# X-DO10_V1_0.net
KiCad netlist of a schematic drawn in Altium Designer
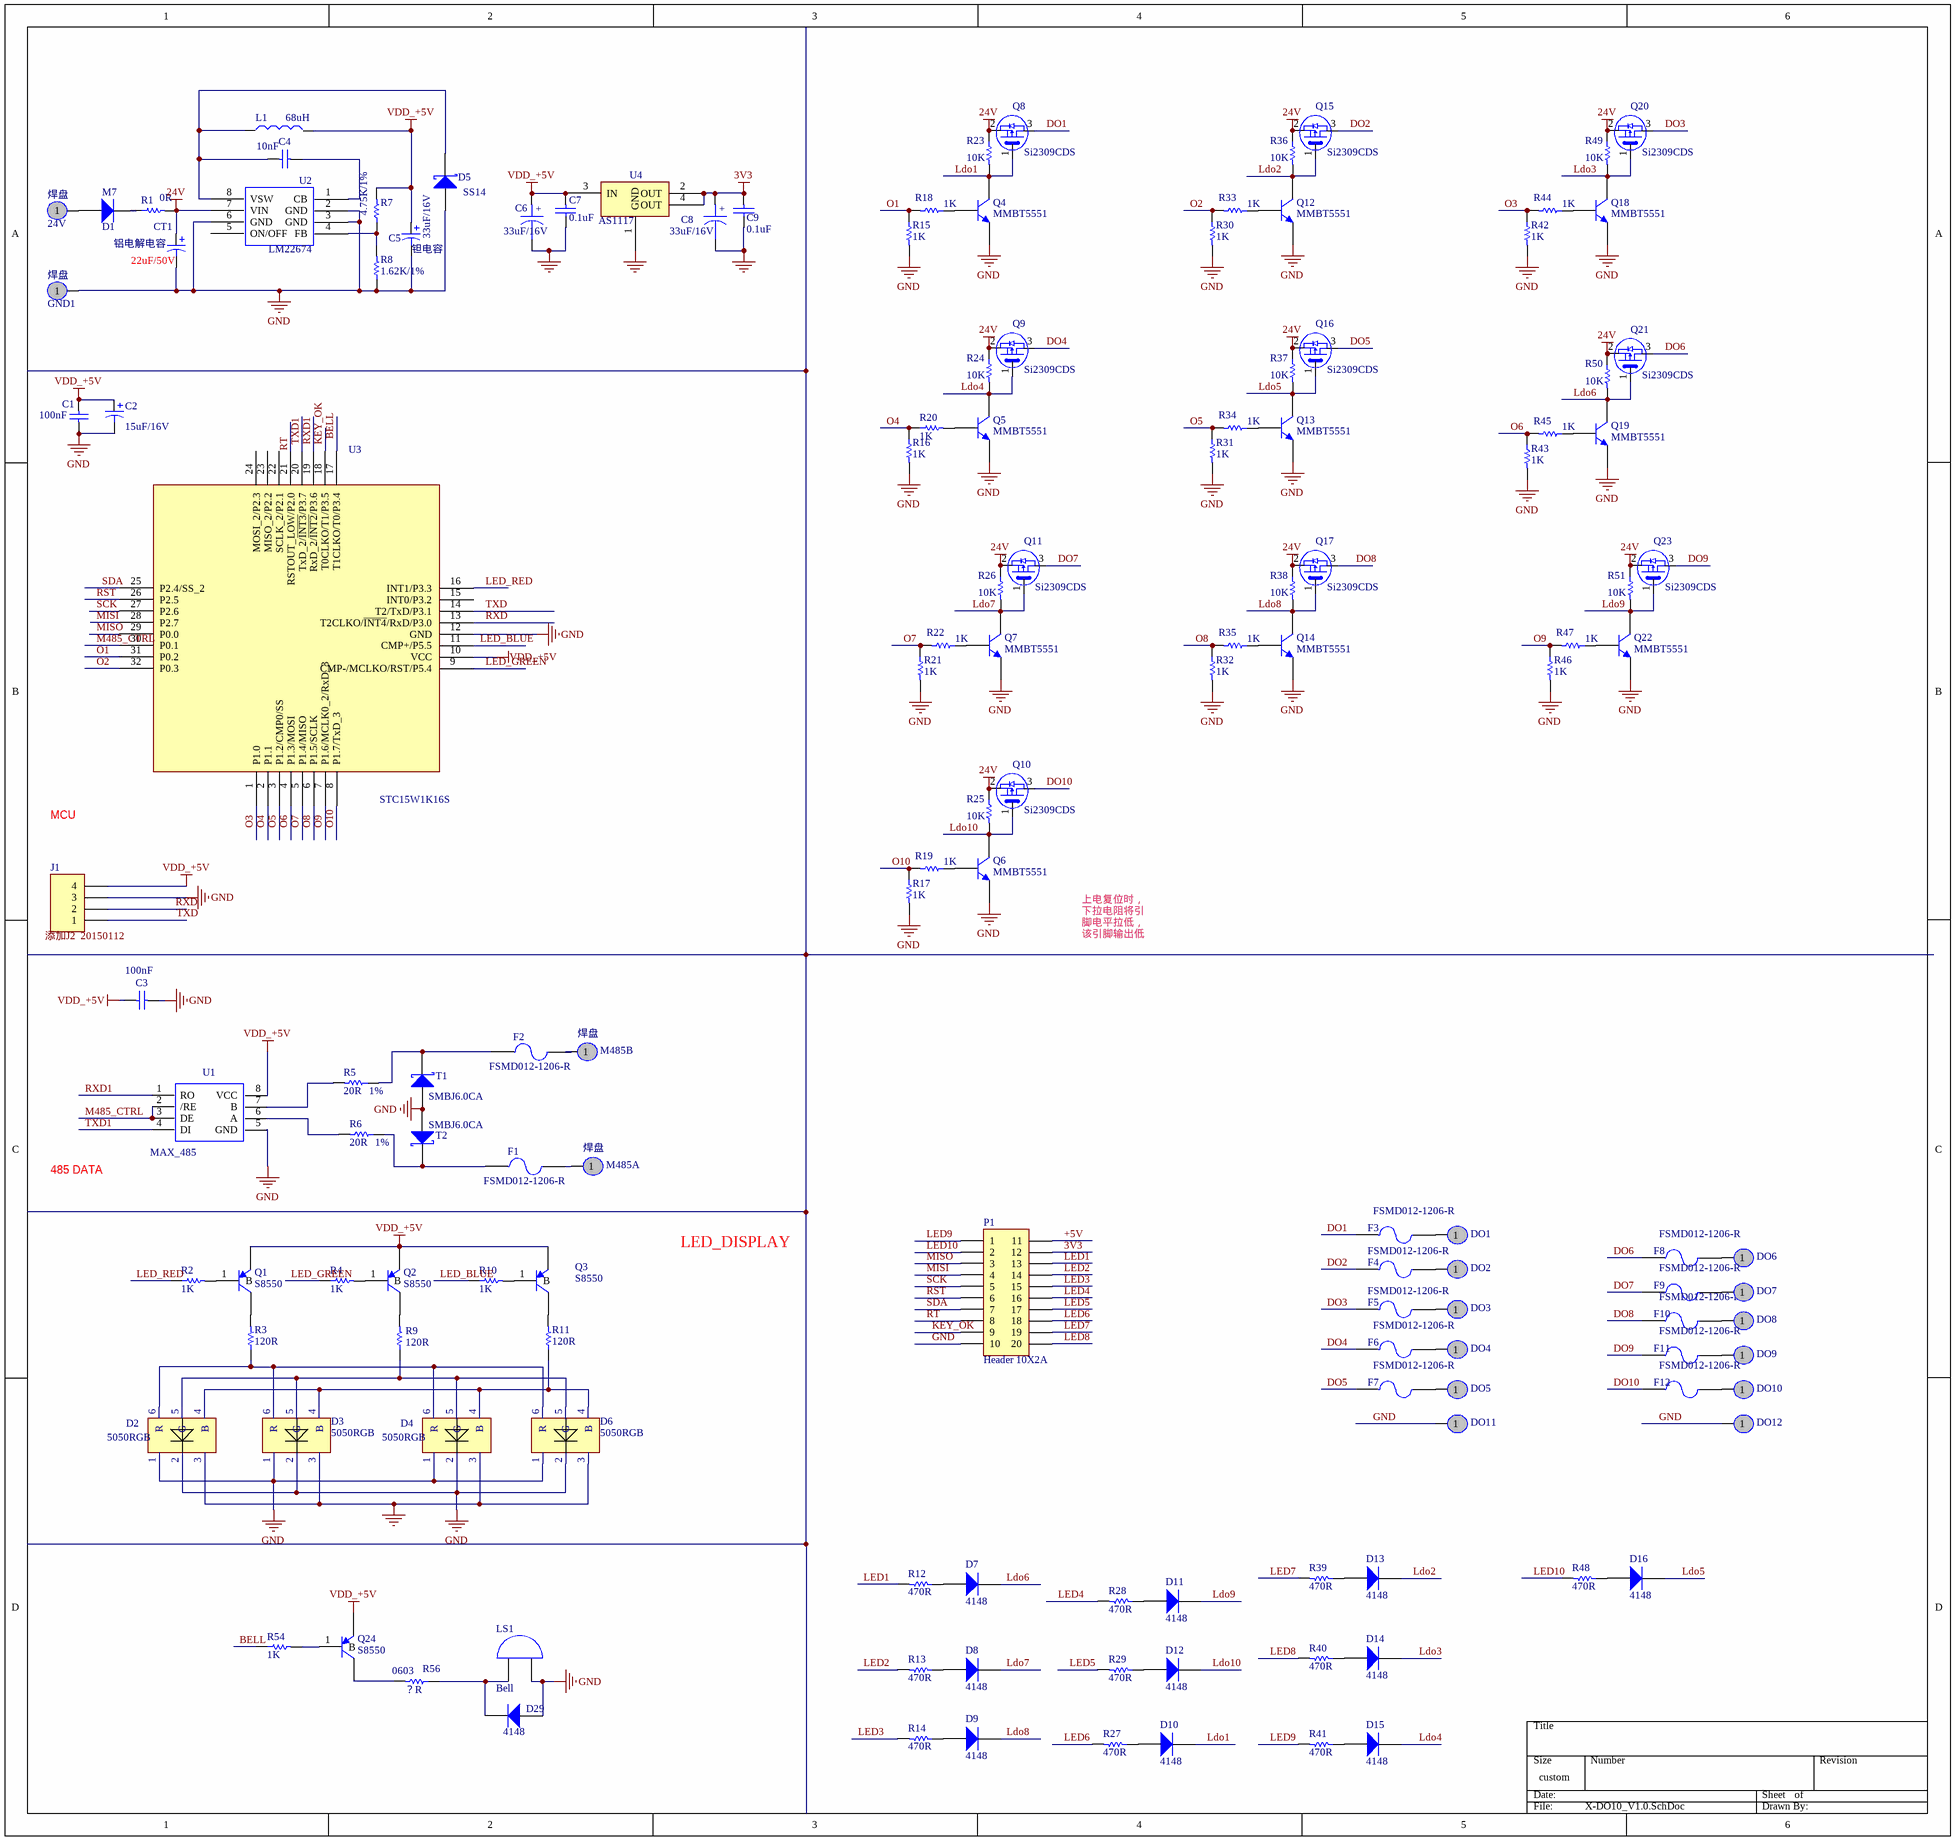
[diagram p0: X-DO10_V1.0.SchDoc]

(export (version "E")
  (design (tool "Eeschema 10.0.6"))
  (components
    (comp (ref "24V") (value "焊盘") (footprint "HOLE_SMD") (libsource (lib "MODBUS_V1.0") (part "焊盘")))
    (comp (ref "C1")
      (value "100nF")
      (footprint "C0603")
      (description "Capacitor")
      (libsource (lib "Miscellaneous Devices") (part "Cap"))
    )
    (comp (ref "C2")
      (value "15uF/16V")
      (footprint "1206C")
      (description "Polarized Capacitor (Radial)")
      (libsource (lib "Miscellaneous Devices") (part "Cap Pol1"))
    )
    (comp (ref "C3")
      (value "~")
      (footprint "C0603")
      (description "Capacitor")
      (fields (field (name "ALTIUM_UNNAMED_1") "100nF"))
      (libsource (lib "Miscellaneous Devices") (part "Cap"))
    )
    (comp (ref "C4")
      (value "~")
      (footprint "C0603")
      (description "Capacitor")
      (fields (field (name "ALTIUM_UNNAMED_1") "10nF"))
      (libsource (lib "Miscellaneous Devices") (part "Cap"))
    )
    (comp (ref "C5")
      (value "钽电容")
      (footprint "CT3528")
      (description "Polarized Capacitor (Radial)")
      (fields (field (name "ALTIUM_VALUE") "33uF/16V"))
      (libsource (lib "Miscellaneous Devices") (part "Cap Pol1"))
    )
    (comp (ref "C6")
      (value "33uF/16V")
      (footprint "CT3528")
      (description "Capacitor")
      (libsource (lib "*") (part "CAPACITOR POL"))
    )
    (comp (ref "C7")
      (value "0.1uF")
      (footprint "C0603")
      (description "Capacitor")
      (libsource (lib "*") (part "CAP"))
    )
    (comp (ref "C8")
      (value "33uF/16V")
      (footprint "CT3528")
      (description "Capacitor")
      (libsource (lib "*") (part "CAPACITOR POL"))
    )
    (comp (ref "C9")
      (value "0.1uF")
      (footprint "C0603")
      (description "Capacitor")
      (libsource (lib "*") (part "CAP"))
    )
    (comp (ref "CT1")
      (value "铝电解电容")
      (footprint "RB0.1")
      (description "Polarized Capacitor (Radial)")
      (fields (field (name "ALTIUM_UNNAMED_1") "22uF/50V"))
      (libsource (lib "Miscellaneous Devices") (part "Cap Pol1"))
    )
    (comp (ref "D1")
      (value "~")
      (footprint "SMB")
      (description "Default Diode")
      (fields (field (name "ALTIUM_UNNAMED_1") "M7"))
      (libsource (lib "Miscellaneous Devices") (part "Diode"))
    )
    (comp (ref "D2") (value "5050RGB") (footprint "5050RGB") (libsource (lib "*") (part "5050RGB")))
    (comp (ref "D3") (value "5050RGB") (footprint "5050RGB") (libsource (lib "*") (part "5050RGB")))
    (comp (ref "D4") (value "5050RGB") (footprint "5050RGB") (libsource (lib "*") (part "5050RGB")))
    (comp (ref "D5")
      (value "~")
      (footprint "SMB")
      (fields (field (name "ALTIUM_UNNAMED_1") "SS14"))
      (libsource (lib "MODBUS_V1.0") (part "SMBJ6.0CA"))
    )
    (comp (ref "D6") (value "5050RGB") (footprint "5050RGB") (libsource (lib "*") (part "5050RGB")))
    (comp (ref "D7")
      (value "~")
      (footprint "1206d")
      (description "Default Diode")
      (fields (field (name "ALTIUM_UNNAMED_1") "4148"))
      (libsource (lib "Miscellaneous Devices") (part "Diode"))
    )
    (comp (ref "D8")
      (value "~")
      (footprint "1206d")
      (description "Default Diode")
      (fields (field (name "ALTIUM_UNNAMED_1") "4148"))
      (libsource (lib "Miscellaneous Devices") (part "Diode"))
    )
    (comp (ref "D9")
      (value "~")
      (footprint "1206d")
      (description "Default Diode")
      (fields (field (name "ALTIUM_UNNAMED_1") "4148"))
      (libsource (lib "Miscellaneous Devices") (part "Diode"))
    )
    (comp (ref "D10")
      (value "~")
      (footprint "1206d")
      (description "Default Diode")
      (fields (field (name "ALTIUM_UNNAMED_1") "4148"))
      (libsource (lib "Miscellaneous Devices") (part "Diode"))
    )
    (comp (ref "D11")
      (value "~")
      (footprint "1206d")
      (description "Default Diode")
      (fields (field (name "ALTIUM_UNNAMED_1") "4148"))
      (libsource (lib "Miscellaneous Devices") (part "Diode"))
    )
    (comp (ref "D12")
      (value "~")
      (footprint "1206d")
      (description "Default Diode")
      (fields (field (name "ALTIUM_UNNAMED_1") "4148"))
      (libsource (lib "Miscellaneous Devices") (part "Diode"))
    )
    (comp (ref "D13")
      (value "~")
      (footprint "1206d")
      (description "Default Diode")
      (fields (field (name "ALTIUM_UNNAMED_1") "4148"))
      (libsource (lib "Miscellaneous Devices") (part "Diode"))
    )
    (comp (ref "D14")
      (value "~")
      (footprint "1206d")
      (description "Default Diode")
      (fields (field (name "ALTIUM_UNNAMED_1") "4148"))
      (libsource (lib "Miscellaneous Devices") (part "Diode"))
    )
    (comp (ref "D15")
      (value "~")
      (footprint "1206d")
      (description "Default Diode")
      (fields (field (name "ALTIUM_UNNAMED_1") "4148"))
      (libsource (lib "Miscellaneous Devices") (part "Diode"))
    )
    (comp (ref "D16")
      (value "~")
      (footprint "1206D")
      (description "Default Diode")
      (fields (field (name "ALTIUM_UNNAMED_1") "4148"))
      (libsource (lib "Miscellaneous Devices") (part "Diode"))
    )
    (comp (ref "D29")
      (value "4148")
      (footprint "MODBUS_V2.0:1206D")
      (description "Default Diode")
      (fields (field (name "PUBLISHER") "Altium Limited"))
      (libsource (lib "Miscellaneous Devices") (part "Diode"))
    )
    (comp (ref "DO1")
      (value "焊盘")
      (footprint "MODBUS_V1.0:HOLE_SMD")
      (libsource (lib "MODBUS_V1.0") (part "焊盘"))
    )
    (comp (ref "DO2")
      (value "焊盘")
      (footprint "MODBUS_V1.0:HOLE_SMD")
      (libsource (lib "MODBUS_V1.0") (part "焊盘"))
    )
    (comp (ref "DO3") (value "焊盘") (footprint "HOLE_SMD") (libsource (lib "MODBUS_V1.0") (part "焊盘")))
    (comp (ref "DO4") (value "焊盘") (footprint "HOLE_SMD") (libsource (lib "MODBUS_V1.0") (part "焊盘")))
    (comp (ref "DO5") (value "焊盘") (footprint "HOLE_SMD") (libsource (lib "MODBUS_V1.0") (part "焊盘")))
    (comp (ref "DO6") (value "焊盘") (footprint "HOLE_SMD") (libsource (lib "MODBUS_V1.0") (part "焊盘")))
    (comp (ref "DO7")
      (value "焊盘")
      (footprint "MODBUS_V1.0:HOLE_SMD")
      (libsource (lib "MODBUS_V1.0") (part "焊盘"))
    )
    (comp (ref "DO8") (value "焊盘") (footprint "HOLE_SMD") (libsource (lib "MODBUS_V1.0") (part "焊盘")))
    (comp (ref "DO9") (value "焊盘") (footprint "HOLE_SMD") (libsource (lib "MODBUS_V1.0") (part "焊盘")))
    (comp (ref "DO10") (value "焊盘") (footprint "HOLE_SMD") (libsource (lib "MODBUS_V1.0") (part "焊盘")))
    (comp (ref "DO11") (value "焊盘") (footprint "HOLE_SMD") (libsource (lib "MODBUS_V1.0") (part "焊盘")))
    (comp (ref "DO12") (value "焊盘") (footprint "HOLE_SMD") (libsource (lib "MODBUS_V1.0") (part "焊盘")))
    (comp (ref "F1")
      (value "FSMD012-1206-R")
      (footprint "1206")
      (description "Fuse")
      (fields (field (name "ALTIUM_UNNAMED_1") "FSMD012-1206-R"))
      (libsource (lib "Miscellaneous Devices") (part "Fuse 2"))
    )
    (comp (ref "F2")
      (value "FSMD012-1206-R")
      (footprint "1206")
      (description "Fuse")
      (fields (field (name "ALTIUM_UNNAMED_1") "FSMD012-1206-R"))
      (libsource (lib "Miscellaneous Devices") (part "Fuse 2"))
    )
    (comp (ref "F3")
      (value "FSMD012-1206-R")
      (footprint "1206")
      (description "Fuse")
      (libsource (lib "Miscellaneous Devices") (part "Fuse 2"))
    )
    (comp (ref "F4")
      (value "FSMD012-1206-R")
      (footprint "1206")
      (description "Fuse")
      (libsource (lib "Miscellaneous Devices") (part "Fuse 2"))
    )
    (comp (ref "F5")
      (value "FSMD012-1206-R")
      (footprint "1206")
      (description "Fuse")
      (libsource (lib "Miscellaneous Devices") (part "Fuse 2"))
    )
    (comp (ref "F6")
      (value "FSMD012-1206-R")
      (footprint "1206")
      (description "Fuse")
      (libsource (lib "Miscellaneous Devices") (part "Fuse 2"))
    )
    (comp (ref "F7")
      (value "FSMD012-1206-R")
      (footprint "1206")
      (description "Fuse")
      (libsource (lib "Miscellaneous Devices") (part "Fuse 2"))
    )
    (comp (ref "F8")
      (value "FSMD012-1206-R")
      (footprint "1206")
      (description "Fuse")
      (libsource (lib "Miscellaneous Devices") (part "Fuse 2"))
    )
    (comp (ref "F9")
      (value "FSMD012-1206-R")
      (footprint "1206")
      (description "Fuse")
      (libsource (lib "Miscellaneous Devices") (part "Fuse 2"))
    )
    (comp (ref "F10")
      (value "FSMD012-1206-R")
      (footprint "1206")
      (description "Fuse")
      (libsource (lib "Miscellaneous Devices") (part "Fuse 2"))
    )
    (comp (ref "F11")
      (value "FSMD012-1206-R")
      (footprint "1206")
      (description "Fuse")
      (libsource (lib "Miscellaneous Devices") (part "Fuse 2"))
    )
    (comp (ref "F12")
      (value "FSMD012-1206-R")
      (footprint "1206")
      (description "Fuse")
      (libsource (lib "Miscellaneous Devices") (part "Fuse 2"))
    )
    (comp (ref "GND1") (value "焊盘") (footprint "HOLE_SMD") (libsource (lib "MODBUS_V1.0") (part "焊盘")))
    (comp (ref "J1")
      (value "~")
      (footprint "SIP4-2.0")
      (libsource (lib "Miscellaneous Connectors") (part "Header 4"))
    )
    (comp (ref "L1")
      (value "~")
      (footprint "L-6X6")
      (fields (field (name "ALTIUM_UNNAMED_1") "68uH"))
      (libsource (lib "MODBUS_V1.0") (part "电感"))
    )
    (comp (ref "LS1")
      (value "Bell")
      (footprint "Bell_DIP_9mm")
      (description "Electrical Bell")
      (fields (field (name "PUBLISHER") "Altium Limited"))
      (libsource (lib "Miscellaneous Devices") (part "Bell"))
    )
    (comp (ref "M485A") (value "焊盘") (footprint "HOLE_SMD") (libsource (lib "MODBUS_V1.0") (part "焊盘")))
    (comp (ref "M485B") (value "焊盘") (footprint "HOLE_SMD") (libsource (lib "MODBUS_V1.0") (part "焊盘")))
    (comp (ref "P1")
      (value "Header 10X2A")
      (footprint "DIP2.0 2*10")
      (description "Header, 10-Pin, Dual row")
      (fields (field (name "PUBLISHER") "Altium Limited"))
      (libsource (lib "Miscellaneous Connectors") (part "Header 10X2A"))
    )
    (comp (ref "Q1") (value "S8550") (footprint "SOT-23") (libsource (lib "*") (part "S8550")))
    (comp (ref "Q2") (value "S8550") (footprint "SOT-23") (libsource (lib "*") (part "S8550")))
    (comp (ref "Q3") (value "S8550") (footprint "SOT-23") (libsource (lib "*") (part "S8550")))
    (comp (ref "Q4")
      (value "MMBT5551")
      (footprint "SOT-23")
      (description "NPN Bipolar Transistor")
      (fields (field (name "PUBLISHER") "Altium Limited"))
      (libsource (lib "Miscellaneous Devices") (part "NPN"))
    )
    (comp (ref "Q5")
      (value "MMBT5551")
      (footprint "SOT-23")
      (description "NPN Bipolar Transistor")
      (fields (field (name "PUBLISHER") "Altium Limited"))
      (libsource (lib "Miscellaneous Devices") (part "NPN"))
    )
    (comp (ref "Q6")
      (value "MMBT5551")
      (footprint "SOT-23")
      (description "NPN Bipolar Transistor")
      (fields (field (name "PUBLISHER") "Altium Limited"))
      (libsource (lib "Miscellaneous Devices") (part "NPN"))
    )
    (comp (ref "Q7")
      (value "MMBT5551")
      (footprint "SOT-23")
      (description "NPN Bipolar Transistor")
      (fields (field (name "PUBLISHER") "Altium Limited"))
      (libsource (lib "Miscellaneous Devices") (part "NPN"))
    )
    (comp (ref "Q8") (value "Si2309CDS") (footprint "SOT-23") (libsource (lib "BATTERY") (part "P-MOSFET")))
    (comp (ref "Q9") (value "Si2309CDS") (footprint "SOT-23") (libsource (lib "BATTERY") (part "P-MOSFET")))
    (comp (ref "Q10") (value "Si2309CDS") (footprint "SOT-23") (libsource (lib "BATTERY") (part "P-MOSFET")))
    (comp (ref "Q11") (value "Si2309CDS") (footprint "SOT-23") (libsource (lib "BATTERY") (part "P-MOSFET")))
    (comp (ref "Q12")
      (value "MMBT5551")
      (footprint "SOT-23")
      (description "NPN Bipolar Transistor")
      (fields (field (name "PUBLISHER") "Altium Limited"))
      (libsource (lib "Miscellaneous Devices") (part "NPN"))
    )
    (comp (ref "Q13")
      (value "MMBT5551")
      (footprint "SOT-23")
      (description "NPN Bipolar Transistor")
      (fields (field (name "PUBLISHER") "Altium Limited"))
      (libsource (lib "Miscellaneous Devices") (part "NPN"))
    )
    (comp (ref "Q14")
      (value "MMBT5551")
      (footprint "SOT-23")
      (description "NPN Bipolar Transistor")
      (fields (field (name "PUBLISHER") "Altium Limited"))
      (libsource (lib "Miscellaneous Devices") (part "NPN"))
    )
    (comp (ref "Q15") (value "Si2309CDS") (footprint "SOT-23") (libsource (lib "BATTERY") (part "P-MOSFET")))
    (comp (ref "Q16") (value "Si2309CDS") (footprint "SOT-23") (libsource (lib "BATTERY") (part "P-MOSFET")))
    (comp (ref "Q17") (value "Si2309CDS") (footprint "SOT-23") (libsource (lib "BATTERY") (part "P-MOSFET")))
    (comp (ref "Q18")
      (value "MMBT5551")
      (footprint "SOT-23")
      (description "NPN Bipolar Transistor")
      (fields (field (name "PUBLISHER") "Altium Limited"))
      (libsource (lib "Miscellaneous Devices") (part "NPN"))
    )
    (comp (ref "Q19")
      (value "MMBT5551")
      (footprint "SOT-23")
      (description "NPN Bipolar Transistor")
      (fields (field (name "PUBLISHER") "Altium Limited"))
      (libsource (lib "Miscellaneous Devices") (part "NPN"))
    )
    (comp (ref "Q20") (value "Si2309CDS") (footprint "SOT-23") (libsource (lib "BATTERY") (part "P-MOSFET")))
    (comp (ref "Q21") (value "Si2309CDS") (footprint "SOT-23") (libsource (lib "BATTERY") (part "P-MOSFET")))
    (comp (ref "Q22")
      (value "MMBT5551")
      (footprint "SOT-23")
      (description "NPN Bipolar Transistor")
      (fields (field (name "PUBLISHER") "Altium Limited"))
      (libsource (lib "Miscellaneous Devices") (part "NPN"))
    )
    (comp (ref "Q23") (value "Si2309CDS") (footprint "SOT-23") (libsource (lib "BATTERY") (part "P-MOSFET")))
    (comp (ref "Q24") (value "S8550") (footprint "SOT-23") (libsource (lib "MODBUS_V1.0") (part "S8550")))
    (comp (ref "R1")
      (value "贴片电阻")
      (footprint "1206")
      (description "Semiconductor Resistor")
      (fields (field (name "ALTIUM_UNNAMED_1") "0R"))
      (libsource (lib "Miscellaneous Devices") (part "Res Semi"))
    )
    (comp (ref "R2")
      (value "1K")
      (footprint "R0603")
      (description "Semiconductor Resistor")
      (libsource (lib "*") (part "Res Semi"))
    )
    (comp (ref "R3")
      (value "120R")
      (footprint "2010")
      (description "Semiconductor Resistor")
      (libsource (lib "*") (part "Res Semi"))
    )
    (comp (ref "R4")
      (value "1K")
      (footprint "R0603")
      (description "Semiconductor Resistor")
      (libsource (lib "*") (part "Res Semi"))
    )
    (comp (ref "R5")
      (value "~")
      (footprint "2010")
      (description "Semiconductor Resistor")
      (fields (field (name "ALTIUM_UNNAMED_1") "20R   1%"))
      (libsource (lib "Miscellaneous Devices") (part "Res Semi"))
    )
    (comp (ref "R6")
      (value "~")
      (footprint "2010")
      (description "Semiconductor Resistor")
      (fields (field (name "ALTIUM_UNNAMED_1") "20R   1%"))
      (libsource (lib "Miscellaneous Devices") (part "Res Semi"))
    )
    (comp (ref "R7")
      (value "~")
      (footprint "R0603")
      (description "Semiconductor Resistor")
      (fields (field (name "ALTIUM_UNNAMED_1") "4.75K/1%"))
      (libsource (lib "Miscellaneous Devices") (part "Res Semi"))
    )
    (comp (ref "R8")
      (value "~")
      (footprint "R0603")
      (description "Semiconductor Resistor")
      (fields (field (name "V") "1.62K/1%"))
      (libsource (lib "Miscellaneous Devices") (part "Res Semi"))
    )
    (comp (ref "R9")
      (value "120R")
      (footprint "2010")
      (description "Semiconductor Resistor")
      (libsource (lib "*") (part "Res Semi"))
    )
    (comp (ref "R10")
      (value "1K")
      (footprint "R0603")
      (description "Semiconductor Resistor")
      (libsource (lib "*") (part "Res Semi"))
    )
    (comp (ref "R11")
      (value "120R")
      (footprint "2010")
      (description "Semiconductor Resistor")
      (libsource (lib "*") (part "Res Semi"))
    )
    (comp (ref "R12")
      (value "~")
      (footprint "r0603")
      (description "贴片电阻")
      (fields (field (name "型号") "470R"))
      (libsource (lib "Miscellaneous Devices") (part "Res Semi"))
    )
    (comp (ref "R13")
      (value "~")
      (footprint "r0603")
      (description "贴片电阻")
      (fields (field (name "型号") "470R"))
      (libsource (lib "Miscellaneous Devices") (part "Res Semi"))
    )
    (comp (ref "R14")
      (value "~")
      (footprint "r0603")
      (description "贴片电阻")
      (fields (field (name "型号") "470R"))
      (libsource (lib "Miscellaneous Devices") (part "Res Semi"))
    )
    (comp (ref "R15")
      (value "贴片电阻")
      (footprint "R0603")
      (description "Semiconductor Resistor")
      (fields (field (name "ALTIUM_UNNAMED_1") "1K"))
      (libsource (lib "Miscellaneous Devices") (part "Res Semi"))
    )
    (comp (ref "R16")
      (value "贴片电阻")
      (footprint "R0603")
      (description "Semiconductor Resistor")
      (fields (field (name "ALTIUM_UNNAMED_1") "1K"))
      (libsource (lib "Miscellaneous Devices") (part "Res Semi"))
    )
    (comp (ref "R17")
      (value "贴片电阻")
      (footprint "R0603")
      (description "Semiconductor Resistor")
      (fields (field (name "ALTIUM_UNNAMED_1") "1K"))
      (libsource (lib "Miscellaneous Devices") (part "Res Semi"))
    )
    (comp (ref "R18")
      (value "贴片电阻")
      (footprint "R0603")
      (description "Semiconductor Resistor")
      (fields (field (name "ALTIUM_UNNAMED_1") "1K"))
      (libsource (lib "Miscellaneous Devices") (part "Res Semi"))
    )
    (comp (ref "R19")
      (value "贴片电阻")
      (footprint "R0603")
      (description "Semiconductor Resistor")
      (fields (field (name "ALTIUM_UNNAMED_1") "1K"))
      (libsource (lib "Miscellaneous Devices") (part "Res Semi"))
    )
    (comp (ref "R20")
      (value "贴片电阻")
      (footprint "R0603")
      (description "Semiconductor Resistor")
      (fields (field (name "ALTIUM_UNNAMED_1") "1K"))
      (libsource (lib "Miscellaneous Devices") (part "Res Semi"))
    )
    (comp (ref "R21")
      (value "贴片电阻")
      (footprint "R0603")
      (description "Semiconductor Resistor")
      (fields (field (name "ALTIUM_UNNAMED_1") "1K"))
      (libsource (lib "Miscellaneous Devices") (part "Res Semi"))
    )
    (comp (ref "R22")
      (value "贴片电阻")
      (footprint "R0603")
      (description "Semiconductor Resistor")
      (fields (field (name "ALTIUM_UNNAMED_1") "1K"))
      (libsource (lib "Miscellaneous Devices") (part "Res Semi"))
    )
    (comp (ref "R23")
      (value "贴片电阻")
      (footprint "R0603")
      (description "Semiconductor Resistor")
      (fields (field (name "ALTIUM_UNNAMED_1") "10K"))
      (libsource (lib "Miscellaneous Devices") (part "Res Semi"))
    )
    (comp (ref "R24")
      (value "贴片电阻")
      (footprint "R0603")
      (description "Semiconductor Resistor")
      (fields (field (name "ALTIUM_UNNAMED_1") "10K"))
      (libsource (lib "Miscellaneous Devices") (part "Res Semi"))
    )
    (comp (ref "R25")
      (value "贴片电阻")
      (footprint "R0603")
      (description "Semiconductor Resistor")
      (fields (field (name "ALTIUM_UNNAMED_1") "10K"))
      (libsource (lib "Miscellaneous Devices") (part "Res Semi"))
    )
    (comp (ref "R26")
      (value "贴片电阻")
      (footprint "R0603")
      (description "Semiconductor Resistor")
      (fields (field (name "ALTIUM_UNNAMED_1") "10K"))
      (libsource (lib "Miscellaneous Devices") (part "Res Semi"))
    )
    (comp (ref "R27")
      (value "~")
      (footprint "r0603")
      (description "贴片电阻")
      (fields (field (name "型号") "470R"))
      (libsource (lib "Miscellaneous Devices") (part "Res Semi"))
    )
    (comp (ref "R28")
      (value "~")
      (footprint "r0603")
      (description "贴片电阻")
      (fields (field (name "型号") "470R"))
      (libsource (lib "Miscellaneous Devices") (part "Res Semi"))
    )
    (comp (ref "R29")
      (value "~")
      (footprint "r0603")
      (description "贴片电阻")
      (fields (field (name "型号") "470R"))
      (libsource (lib "Miscellaneous Devices") (part "Res Semi"))
    )
    (comp (ref "R30")
      (value "贴片电阻")
      (footprint "R0603")
      (description "Semiconductor Resistor")
      (fields (field (name "ALTIUM_UNNAMED_1") "1K"))
      (libsource (lib "Miscellaneous Devices") (part "Res Semi"))
    )
    (comp (ref "R31")
      (value "贴片电阻")
      (footprint "R0603")
      (description "Semiconductor Resistor")
      (fields (field (name "ALTIUM_UNNAMED_1") "1K"))
      (libsource (lib "Miscellaneous Devices") (part "Res Semi"))
    )
    (comp (ref "R32")
      (value "贴片电阻")
      (footprint "R0603")
      (description "Semiconductor Resistor")
      (fields (field (name "ALTIUM_UNNAMED_1") "1K"))
      (libsource (lib "Miscellaneous Devices") (part "Res Semi"))
    )
    (comp (ref "R33")
      (value "贴片电阻")
      (footprint "R0603")
      (description "Semiconductor Resistor")
      (fields (field (name "ALTIUM_UNNAMED_1") "1K"))
      (libsource (lib "Miscellaneous Devices") (part "Res Semi"))
    )
    (comp (ref "R34")
      (value "贴片电阻")
      (footprint "R0603")
      (description "Semiconductor Resistor")
      (fields (field (name "ALTIUM_UNNAMED_1") "1K"))
      (libsource (lib "Miscellaneous Devices") (part "Res Semi"))
    )
    (comp (ref "R35")
      (value "贴片电阻")
      (footprint "R0603")
      (description "Semiconductor Resistor")
      (fields (field (name "ALTIUM_UNNAMED_1") "1K"))
      (libsource (lib "Miscellaneous Devices") (part "Res Semi"))
    )
    (comp (ref "R36")
      (value "贴片电阻")
      (footprint "R0603")
      (description "Semiconductor Resistor")
      (fields (field (name "ALTIUM_UNNAMED_1") "10K"))
      (libsource (lib "Miscellaneous Devices") (part "Res Semi"))
    )
    (comp (ref "R37")
      (value "贴片电阻")
      (footprint "R0603")
      (description "Semiconductor Resistor")
      (fields (field (name "ALTIUM_UNNAMED_1") "10K"))
      (libsource (lib "Miscellaneous Devices") (part "Res Semi"))
    )
    (comp (ref "R38")
      (value "贴片电阻")
      (footprint "R0603")
      (description "Semiconductor Resistor")
      (fields (field (name "ALTIUM_UNNAMED_1") "10K"))
      (libsource (lib "Miscellaneous Devices") (part "Res Semi"))
    )
    (comp (ref "R39")
      (value "~")
      (footprint "r0603")
      (description "贴片电阻")
      (fields (field (name "型号") "470R"))
      (libsource (lib "Miscellaneous Devices") (part "Res Semi"))
    )
    (comp (ref "R40")
      (value "~")
      (footprint "r0603")
      (description "贴片电阻")
      (fields (field (name "型号") "470R"))
      (libsource (lib "Miscellaneous Devices") (part "Res Semi"))
    )
    (comp (ref "R41")
      (value "~")
      (footprint "r0603")
      (description "贴片电阻")
      (fields (field (name "型号") "470R"))
      (libsource (lib "Miscellaneous Devices") (part "Res Semi"))
    )
    (comp (ref "R42")
      (value "贴片电阻")
      (footprint "R0603")
      (description "Semiconductor Resistor")
      (fields (field (name "ALTIUM_UNNAMED_1") "1K"))
      (libsource (lib "Miscellaneous Devices") (part "Res Semi"))
    )
    (comp (ref "R43")
      (value "贴片电阻")
      (footprint "R0603")
      (description "Semiconductor Resistor")
      (fields (field (name "ALTIUM_UNNAMED_1") "1K"))
      (libsource (lib "Miscellaneous Devices") (part "Res Semi"))
    )
    (comp (ref "R44")
      (value "贴片电阻")
      (footprint "R0603")
      (description "Semiconductor Resistor")
      (fields (field (name "ALTIUM_UNNAMED_1") "1K"))
      (libsource (lib "Miscellaneous Devices") (part "Res Semi"))
    )
    (comp (ref "R45")
      (value "贴片电阻")
      (footprint "R0603")
      (description "Semiconductor Resistor")
      (fields (field (name "ALTIUM_UNNAMED_1") "1K"))
      (libsource (lib "Miscellaneous Devices") (part "Res Semi"))
    )
    (comp (ref "R46")
      (value "贴片电阻")
      (footprint "R0603")
      (description "Semiconductor Resistor")
      (fields (field (name "ALTIUM_UNNAMED_1") "1K"))
      (libsource (lib "Miscellaneous Devices") (part "Res Semi"))
    )
    (comp (ref "R47")
      (value "贴片电阻")
      (footprint "R0603")
      (description "Semiconductor Resistor")
      (fields (field (name "ALTIUM_UNNAMED_1") "1K"))
      (libsource (lib "Miscellaneous Devices") (part "Res Semi"))
    )
    (comp (ref "R48")
      (value "~")
      (footprint "r0603")
      (description "贴片电阻")
      (fields (field (name "型号") "470R"))
      (libsource (lib "Miscellaneous Devices") (part "Res Semi"))
    )
    (comp (ref "R49")
      (value "贴片电阻")
      (footprint "R0603")
      (description "Semiconductor Resistor")
      (fields (field (name "ALTIUM_UNNAMED_1") "10K"))
      (libsource (lib "Miscellaneous Devices") (part "Res Semi"))
    )
    (comp (ref "R50")
      (value "贴片电阻")
      (footprint "R0603")
      (description "Semiconductor Resistor")
      (fields (field (name "ALTIUM_UNNAMED_1") "10K"))
      (libsource (lib "Miscellaneous Devices") (part "Res Semi"))
    )
    (comp (ref "R51")
      (value "贴片电阻")
      (footprint "R0603")
      (description "Semiconductor Resistor")
      (fields (field (name "ALTIUM_UNNAMED_1") "10K"))
      (libsource (lib "Miscellaneous Devices") (part "Res Semi"))
    )
    (comp (ref "R54")
      (value "1K")
      (footprint "R0603")
      (description "Semiconductor Resistor")
      (fields (field (name "PUBLISHER") "Altium Limited"))
      (libsource (lib "Miscellaneous Devices") (part "Res Semi"))
    )
    (comp (ref "R56")
      (value "0603")
      (footprint "R0603")
      (description "Semiconductor Resistor")
      (fields (field (name "ALTIUM_UNNAMED_1") "？R"))
      (libsource (lib "Miscellaneous Devices") (part "Res Semi"))
    )
    (comp (ref "T1")
      (value "SMBJ6.0CA")
      (footprint "HSMA")
      (fields (field (name "ALTIUM_UNNAMED_1") "SMBJ6.0CA"))
      (libsource (lib "MODBUS_V1.0") (part "SMBJ6.0CA"))
    )
    (comp (ref "T2")
      (value "SMBJ6.0CA")
      (footprint "HSMA")
      (fields (field (name "ALTIUM_UNNAMED_1") "SMBJ6.0CA"))
      (libsource (lib "MODBUS_V1.0") (part "SMBJ6.0CA"))
    )
    (comp (ref "U1")
      (value "MAX_485")
      (footprint "SO-1.27-8/4.0")
      (fields (field (name "ALTIUM_UNNAMED_1") "MAX_485"))
      (libsource (lib "*") (part "MAX_485"))
    )
    (comp (ref "U2")
      (value "LM22674")
      (footprint "SO-1.27-9/4.0")
      (fields (field (name "ALTIUM_UNNAMED_1") "LM22674"))
      (libsource (lib "*") (part "2674"))
    )
    (comp (ref "U3")
      (value "STC15W1K16S")
      (footprint "LQFP-0.8-32/9X9")
      (fields (field (name "ALTIUM_UNNAMED_1") "STC15W1K16S"))
      (libsource (lib "MODBUS_V1.0") (part "STC15W1K16S"))
    )
    (comp (ref "U4") (value "AS1117") (footprint "1117") (libsource (lib "*") (part "AS1117")))
  )
  (nets
    (net (code "1") (name "/+5V") (class "Default")
      (node (ref "P1") (pin "11") (pinfunction "11_11") (pintype "passive"))
    )
    (net (code "2") (name "/BELL") (class "Default")
      (node (ref "R54") (pin "1") (pinfunction "1_1") (pintype "passive"))
      (node (ref "U3") (pin "17") (pinfunction "T1CLKO/T0/P3.4_17") (pintype "passive"))
    )
    (net (code "3") (name "/DO1") (class "Default")
      (node (ref "F3") (pin "1") (pinfunction "1_1") (pintype "passive"))
      (node (ref "Q8") (pin "3") (pinfunction "D_3") (pintype "passive"))
    )
    (net (code "4") (name "/DO2") (class "Default")
      (node (ref "F4") (pin "1") (pinfunction "1_1") (pintype "passive"))
      (node (ref "Q15") (pin "3") (pinfunction "D_3") (pintype "passive"))
    )
    (net (code "5") (name "/DO3") (class "Default")
      (node (ref "F5") (pin "1") (pinfunction "1_1") (pintype "passive"))
      (node (ref "Q20") (pin "3") (pinfunction "D_3") (pintype "passive"))
    )
    (net (code "6") (name "/DO4") (class "Default")
      (node (ref "F6") (pin "1") (pinfunction "1_1") (pintype "passive"))
      (node (ref "Q9") (pin "3") (pinfunction "D_3") (pintype "passive"))
    )
    (net (code "7") (name "/DO5") (class "Default")
      (node (ref "F7") (pin "1") (pinfunction "1_1") (pintype "passive"))
      (node (ref "Q16") (pin "3") (pinfunction "D_3") (pintype "passive"))
    )
    (net (code "8") (name "/DO6") (class "Default")
      (node (ref "F8") (pin "1") (pinfunction "1_1") (pintype "passive"))
      (node (ref "Q21") (pin "3") (pinfunction "D_3") (pintype "passive"))
    )
    (net (code "9") (name "/DO7") (class "Default")
      (node (ref "F9") (pin "1") (pinfunction "1_1") (pintype "passive"))
      (node (ref "Q11") (pin "3") (pinfunction "D_3") (pintype "passive"))
    )
    (net (code "10") (name "/DO8") (class "Default")
      (node (ref "F10") (pin "1") (pinfunction "1_1") (pintype "passive"))
      (node (ref "Q17") (pin "3") (pinfunction "D_3") (pintype "passive"))
    )
    (net (code "11") (name "/DO9") (class "Default")
      (node (ref "F11") (pin "1") (pinfunction "1_1") (pintype "passive"))
      (node (ref "Q23") (pin "3") (pinfunction "D_3") (pintype "passive"))
    )
    (net (code "12") (name "/DO10") (class "Default")
      (node (ref "F12") (pin "1") (pinfunction "1_1") (pintype "passive"))
      (node (ref "Q10") (pin "3") (pinfunction "D_3") (pintype "passive"))
    )
    (net (code "13") (name "/KEY_OK") (class "Default")
      (node (ref "P1") (pin "9") (pinfunction "9_9") (pintype "passive"))
      (node (ref "U3") (pin "18") (pinfunction "T0CLKO/T1/P3.5_18") (pintype "passive"))
    )
    (net (code "14") (name "/LED1") (class "Default")
      (node (ref "P1") (pin "13") (pinfunction "13_13") (pintype "passive"))
      (node (ref "R12") (pin "2") (pinfunction "2_2") (pintype "passive"))
    )
    (net (code "15") (name "/LED2") (class "Default")
      (node (ref "P1") (pin "14") (pinfunction "14_14") (pintype "passive"))
      (node (ref "R13") (pin "2") (pinfunction "2_2") (pintype "passive"))
    )
    (net (code "16") (name "/LED3") (class "Default")
      (node (ref "P1") (pin "15") (pinfunction "15_15") (pintype "passive"))
      (node (ref "R14") (pin "2") (pinfunction "2_2") (pintype "passive"))
    )
    (net (code "17") (name "/LED4") (class "Default")
      (node (ref "P1") (pin "16") (pinfunction "16_16") (pintype "passive"))
      (node (ref "R28") (pin "2") (pinfunction "2_2") (pintype "passive"))
    )
    (net (code "18") (name "/LED5") (class "Default")
      (node (ref "P1") (pin "17") (pinfunction "17_17") (pintype "passive"))
      (node (ref "R29") (pin "2") (pinfunction "2_2") (pintype "passive"))
    )
    (net (code "19") (name "/LED6") (class "Default")
      (node (ref "P1") (pin "18") (pinfunction "18_18") (pintype "passive"))
      (node (ref "R27") (pin "2") (pinfunction "2_2") (pintype "passive"))
    )
    (net (code "20") (name "/LED7") (class "Default")
      (node (ref "P1") (pin "19") (pinfunction "19_19") (pintype "passive"))
      (node (ref "R39") (pin "2") (pinfunction "2_2") (pintype "passive"))
    )
    (net (code "21") (name "/LED8") (class "Default")
      (node (ref "P1") (pin "20") (pinfunction "20_20") (pintype "passive"))
      (node (ref "R40") (pin "2") (pinfunction "2_2") (pintype "passive"))
    )
    (net (code "22") (name "/LED9") (class "Default")
      (node (ref "P1") (pin "1") (pinfunction "1_1") (pintype "passive"))
      (node (ref "R41") (pin "2") (pinfunction "2_2") (pintype "passive"))
    )
    (net (code "23") (name "/LED10") (class "Default")
      (node (ref "P1") (pin "2") (pinfunction "2_2") (pintype "passive"))
      (node (ref "R48") (pin "2") (pinfunction "2_2") (pintype "passive"))
    )
    (net (code "24") (name "/LED_BLUE") (class "Default")
      (node (ref "R10") (pin "1") (pinfunction "1_1") (pintype "passive"))
      (node (ref "U3") (pin "11") (pinfunction "CMP+/P5.5_11") (pintype "passive"))
    )
    (net (code "25") (name "/LED_GREEN") (class "Default")
      (node (ref "R4") (pin "1") (pinfunction "1_1") (pintype "passive"))
      (node (ref "U3") (pin "9") (pinfunction "CMP-/MCLKO/RST/P5.4_9") (pintype "passive"))
    )
    (net (code "26") (name "/LED_RED") (class "Default")
      (node (ref "R2") (pin "1") (pinfunction "1_1") (pintype "passive"))
      (node (ref "U3") (pin "16") (pinfunction "INT1/P3.3_16") (pintype "passive"))
    )
    (net (code "27") (name "/Ldo1") (class "Default")
      (node (ref "D10") (pin "2") (pinfunction "K_2") (pintype "passive"))
      (node (ref "Q4") (pin "3") (pinfunction "C_3") (pintype "passive"))
      (node (ref "Q8") (pin "1") (pinfunction "G_1") (pintype "passive"))
      (node (ref "R23") (pin "2") (pinfunction "2_2") (pintype "passive"))
    )
    (net (code "28") (name "/Ldo2") (class "Default")
      (node (ref "D13") (pin "2") (pinfunction "K_2") (pintype "passive"))
      (node (ref "Q12") (pin "3") (pinfunction "C_3") (pintype "passive"))
      (node (ref "Q15") (pin "1") (pinfunction "G_1") (pintype "passive"))
      (node (ref "R36") (pin "2") (pinfunction "2_2") (pintype "passive"))
    )
    (net (code "29") (name "/Ldo3") (class "Default")
      (node (ref "D14") (pin "2") (pinfunction "K_2") (pintype "passive"))
      (node (ref "Q18") (pin "3") (pinfunction "C_3") (pintype "passive"))
      (node (ref "Q20") (pin "1") (pinfunction "G_1") (pintype "passive"))
      (node (ref "R49") (pin "2") (pinfunction "2_2") (pintype "passive"))
    )
    (net (code "30") (name "/Ldo4") (class "Default")
      (node (ref "D15") (pin "2") (pinfunction "K_2") (pintype "passive"))
      (node (ref "Q5") (pin "3") (pinfunction "C_3") (pintype "passive"))
      (node (ref "Q9") (pin "1") (pinfunction "G_1") (pintype "passive"))
      (node (ref "R24") (pin "2") (pinfunction "2_2") (pintype "passive"))
    )
    (net (code "31") (name "/Ldo5") (class "Default")
      (node (ref "D16") (pin "2") (pinfunction "K_2") (pintype "passive"))
      (node (ref "Q13") (pin "3") (pinfunction "C_3") (pintype "passive"))
      (node (ref "Q16") (pin "1") (pinfunction "G_1") (pintype "passive"))
      (node (ref "R37") (pin "2") (pinfunction "2_2") (pintype "passive"))
    )
    (net (code "32") (name "/Ldo6") (class "Default")
      (node (ref "D7") (pin "2") (pinfunction "K_2") (pintype "passive"))
      (node (ref "Q19") (pin "3") (pinfunction "C_3") (pintype "passive"))
      (node (ref "Q21") (pin "1") (pinfunction "G_1") (pintype "passive"))
      (node (ref "R50") (pin "2") (pinfunction "2_2") (pintype "passive"))
    )
    (net (code "33") (name "/Ldo7") (class "Default")
      (node (ref "D8") (pin "2") (pinfunction "K_2") (pintype "passive"))
      (node (ref "Q11") (pin "1") (pinfunction "G_1") (pintype "passive"))
      (node (ref "Q7") (pin "3") (pinfunction "C_3") (pintype "passive"))
      (node (ref "R26") (pin "2") (pinfunction "2_2") (pintype "passive"))
    )
    (net (code "34") (name "/Ldo8") (class "Default")
      (node (ref "D9") (pin "2") (pinfunction "K_2") (pintype "passive"))
      (node (ref "Q14") (pin "3") (pinfunction "C_3") (pintype "passive"))
      (node (ref "Q17") (pin "1") (pinfunction "G_1") (pintype "passive"))
      (node (ref "R38") (pin "2") (pinfunction "2_2") (pintype "passive"))
    )
    (net (code "35") (name "/Ldo9") (class "Default")
      (node (ref "D11") (pin "2") (pinfunction "K_2") (pintype "passive"))
      (node (ref "Q22") (pin "3") (pinfunction "C_3") (pintype "passive"))
      (node (ref "Q23") (pin "1") (pinfunction "G_1") (pintype "passive"))
      (node (ref "R51") (pin "2") (pinfunction "2_2") (pintype "passive"))
    )
    (net (code "36") (name "/Ldo10") (class "Default")
      (node (ref "D12") (pin "2") (pinfunction "K_2") (pintype "passive"))
      (node (ref "Q10") (pin "1") (pinfunction "G_1") (pintype "passive"))
      (node (ref "Q6") (pin "3") (pinfunction "C_3") (pintype "passive"))
      (node (ref "R25") (pin "2") (pinfunction "2_2") (pintype "passive"))
    )
    (net (code "37") (name "/M485_CTRL") (class "Default")
      (node (ref "U1") (pin "2") (pinfunction "/RE_2") (pintype "passive"))
      (node (ref "U1") (pin "3") (pinfunction "DE_3") (pintype "passive"))
      (node (ref "U3") (pin "30") (pinfunction "P0.1_30") (pintype "passive"))
    )
    (net (code "38") (name "/MISI") (class "Default")
      (node (ref "P1") (pin "4") (pinfunction "4_4") (pintype "passive"))
      (node (ref "U3") (pin "28") (pinfunction "P2.7_28") (pintype "passive"))
    )
    (net (code "39") (name "/MISO") (class "Default")
      (node (ref "P1") (pin "3") (pinfunction "3_3") (pintype "passive"))
      (node (ref "U3") (pin "29") (pinfunction "P0.0_29") (pintype "passive"))
    )
    (net (code "40") (name "/O1") (class "Default")
      (node (ref "R15") (pin "1") (pinfunction "1_1") (pintype "passive"))
      (node (ref "R18") (pin "2") (pinfunction "2_2") (pintype "passive"))
      (node (ref "U3") (pin "31") (pinfunction "P0.2_31") (pintype "passive"))
    )
    (net (code "41") (name "/O2") (class "Default")
      (node (ref "R30") (pin "1") (pinfunction "1_1") (pintype "passive"))
      (node (ref "R33") (pin "2") (pinfunction "2_2") (pintype "passive"))
      (node (ref "U3") (pin "32") (pinfunction "P0.3_32") (pintype "passive"))
    )
    (net (code "42") (name "/O3") (class "Default")
      (node (ref "R42") (pin "1") (pinfunction "1_1") (pintype "passive"))
      (node (ref "R44") (pin "2") (pinfunction "2_2") (pintype "passive"))
      (node (ref "U3") (pin "1") (pinfunction "P1.0_1") (pintype "passive"))
    )
    (net (code "43") (name "/O4") (class "Default")
      (node (ref "R16") (pin "1") (pinfunction "1_1") (pintype "passive"))
      (node (ref "R20") (pin "1") (pinfunction "1_1") (pintype "passive"))
      (node (ref "U3") (pin "2") (pinfunction "P1.1_2") (pintype "passive"))
    )
    (net (code "44") (name "/O5") (class "Default")
      (node (ref "R31") (pin "1") (pinfunction "1_1") (pintype "passive"))
      (node (ref "R34") (pin "2") (pinfunction "2_2") (pintype "passive"))
      (node (ref "U3") (pin "3") (pinfunction "P1.2/CMP0/SS_3") (pintype "passive"))
    )
    (net (code "45") (name "/O6") (class "Default")
      (node (ref "R43") (pin "1") (pinfunction "1_1") (pintype "passive"))
      (node (ref "R45") (pin "2") (pinfunction "2_2") (pintype "passive"))
      (node (ref "U3") (pin "4") (pinfunction "P1.3/MOSI_4") (pintype "passive"))
    )
    (net (code "46") (name "/O7") (class "Default")
      (node (ref "R21") (pin "1") (pinfunction "1_1") (pintype "passive"))
      (node (ref "R22") (pin "2") (pinfunction "2_2") (pintype "passive"))
      (node (ref "U3") (pin "5") (pinfunction "P1.4/MISO_5") (pintype "passive"))
    )
    (net (code "47") (name "/O8") (class "Default")
      (node (ref "R32") (pin "1") (pinfunction "1_1") (pintype "passive"))
      (node (ref "R35") (pin "2") (pinfunction "2_2") (pintype "passive"))
      (node (ref "U3") (pin "6") (pinfunction "P1.5/SCLK_6") (pintype "passive"))
    )
    (net (code "48") (name "/O9") (class "Default")
      (node (ref "R46") (pin "1") (pinfunction "1_1") (pintype "passive"))
      (node (ref "R47") (pin "2") (pinfunction "2_2") (pintype "passive"))
      (node (ref "U3") (pin "7") (pinfunction "P1.6/MCLK0_2/RxD_3_7") (pintype "passive"))
    )
    (net (code "49") (name "/O10") (class "Default")
      (node (ref "R17") (pin "1") (pinfunction "1_1") (pintype "passive"))
      (node (ref "R19") (pin "2") (pinfunction "2_2") (pintype "passive"))
      (node (ref "U3") (pin "8") (pinfunction "P1.7/TxD_3_8") (pintype "passive"))
    )
    (net (code "50") (name "/RST") (class "Default")
      (node (ref "P1") (pin "6") (pinfunction "6_6") (pintype "passive"))
      (node (ref "U3") (pin "26") (pinfunction "P2.5_26") (pintype "passive"))
    )
    (net (code "51") (name "/RT") (class "Default")
      (node (ref "P1") (pin "8") (pinfunction "8_8") (pintype "passive"))
      (node (ref "U3") (pin "21") (pinfunction "RSTOUT_LOW/P2.0_21") (pintype "passive"))
    )
    (net (code "52") (name "/RXD") (class "Default")
      (node (ref "J1") (pin "2") (pinfunction "2_2") (pintype "passive"))
      (node (ref "U3") (pin "13") (pinfunction "T2CLKO/~{INT4}/RxD/P3.0_13") (pintype "passive"))
    )
    (net (code "53") (name "/RXD1") (class "Default")
      (node (ref "U1") (pin "1") (pinfunction "RO_1") (pintype "passive"))
      (node (ref "U3") (pin "19") (pinfunction "RxD_2/~{INT2}/P3.6_19") (pintype "passive"))
    )
    (net (code "54") (name "/SCK") (class "Default")
      (node (ref "P1") (pin "5") (pinfunction "5_5") (pintype "passive"))
      (node (ref "U3") (pin "27") (pinfunction "P2.6_27") (pintype "passive"))
    )
    (net (code "55") (name "/SDA") (class "Default")
      (node (ref "P1") (pin "7") (pinfunction "7_7") (pintype "passive"))
      (node (ref "U3") (pin "25") (pinfunction "P2.4/SS_2_25") (pintype "passive"))
    )
    (net (code "56") (name "/TXD") (class "Default")
      (node (ref "J1") (pin "1") (pinfunction "1_1") (pintype "passive"))
      (node (ref "U3") (pin "14") (pinfunction "T2/TxD/P3.1_14") (pintype "passive"))
    )
    (net (code "57") (name "/TXD1") (class "Default")
      (node (ref "U1") (pin "4") (pinfunction "DI_4") (pintype "passive"))
      (node (ref "U3") (pin "20") (pinfunction "TxD_2/~{INT3}/P3.7_20") (pintype "passive"))
    )
    (net (code "58") (name "3V3") (class "Default")
      (node (ref "C8") (pin "1") (pinfunction "1_1") (pintype "passive"))
      (node (ref "C9") (pin "1") (pinfunction "1_1") (pintype "passive"))
      (node (ref "P1") (pin "12") (pinfunction "12_12") (pintype "passive"))
      (node (ref "U4") (pin "2") (pinfunction "OUT_2") (pintype "passive"))
      (node (ref "U4") (pin "4") (pinfunction "OUT_4") (pintype "passive"))
    )
    (net (code "59") (name "24V") (class "Default")
      (node (ref "CT1") (pin "1") (pinfunction "1_1") (pintype "passive"))
      (node (ref "Q10") (pin "2") (pinfunction "S_2") (pintype "passive"))
      (node (ref "Q11") (pin "2") (pinfunction "S_2") (pintype "passive"))
      (node (ref "Q15") (pin "2") (pinfunction "S_2") (pintype "passive"))
      (node (ref "Q16") (pin "2") (pinfunction "S_2") (pintype "passive"))
      (node (ref "Q17") (pin "2") (pinfunction "S_2") (pintype "passive"))
      (node (ref "Q20") (pin "2") (pinfunction "S_2") (pintype "passive"))
      (node (ref "Q21") (pin "2") (pinfunction "S_2") (pintype "passive"))
      (node (ref "Q23") (pin "2") (pinfunction "S_2") (pintype "passive"))
      (node (ref "Q8") (pin "2") (pinfunction "S_2") (pintype "passive"))
      (node (ref "Q9") (pin "2") (pinfunction "S_2") (pintype "passive"))
      (node (ref "R1") (pin "2") (pinfunction "2_2") (pintype "passive"))
      (node (ref "R23") (pin "1") (pinfunction "1_1") (pintype "passive"))
      (node (ref "R24") (pin "1") (pinfunction "1_1") (pintype "passive"))
      (node (ref "R25") (pin "1") (pinfunction "1_1") (pintype "passive"))
      (node (ref "R26") (pin "1") (pinfunction "1_1") (pintype "passive"))
      (node (ref "R36") (pin "1") (pinfunction "1_1") (pintype "passive"))
      (node (ref "R37") (pin "1") (pinfunction "1_1") (pintype "passive"))
      (node (ref "R38") (pin "1") (pinfunction "1_1") (pintype "passive"))
      (node (ref "R49") (pin "1") (pinfunction "1_1") (pintype "passive"))
      (node (ref "R50") (pin "1") (pinfunction "1_1") (pintype "passive"))
      (node (ref "R51") (pin "1") (pinfunction "1_1") (pintype "passive"))
      (node (ref "U2") (pin "7") (pinfunction "VIN_7") (pintype "passive"))
    )
    (net (code "60") (name "GND") (class "Default")
      (node (ref "C1") (pin "1") (pinfunction "1_1") (pintype "passive"))
      (node (ref "C2") (pin "2") (pinfunction "2_2") (pintype "passive"))
      (node (ref "C3") (pin "1") (pinfunction "1_1") (pintype "passive"))
      (node (ref "C5") (pin "2") (pinfunction "2_2") (pintype "passive"))
      (node (ref "C6") (pin "2") (pinfunction "2_2") (pintype "passive"))
      (node (ref "C7") (pin "2") (pinfunction "2_2") (pintype "passive"))
      (node (ref "C8") (pin "2") (pinfunction "2_2") (pintype "passive"))
      (node (ref "C9") (pin "2") (pinfunction "2_2") (pintype "passive"))
      (node (ref "CT1") (pin "2") (pinfunction "2_2") (pintype "passive"))
      (node (ref "D2") (pin "1") (pintype "passive"))
      (node (ref "D2") (pin "2") (pintype "passive"))
      (node (ref "D2") (pin "3") (pintype "passive"))
      (node (ref "D29") (pin "1") (pinfunction "A_1") (pintype "passive"))
      (node (ref "D3") (pin "1") (pintype "passive"))
      (node (ref "D3") (pin "2") (pintype "passive"))
      (node (ref "D3") (pin "3") (pintype "passive"))
      (node (ref "D4") (pin "1") (pintype "passive"))
      (node (ref "D4") (pin "2") (pintype "passive"))
      (node (ref "D4") (pin "3") (pintype "passive"))
      (node (ref "D5") (pin "1") (pinfunction "A_1") (pintype "passive"))
      (node (ref "D6") (pin "1") (pintype "passive"))
      (node (ref "D6") (pin "2") (pintype "passive"))
      (node (ref "D6") (pin "3") (pintype "passive"))
      (node (ref "DO11") (pin "1") (pinfunction "1_1") (pintype "passive"))
      (node (ref "DO12") (pin "1") (pinfunction "1_1") (pintype "passive"))
      (node (ref "GND1") (pin "1") (pinfunction "1_1") (pintype "passive"))
      (node (ref "J1") (pin "3") (pinfunction "3_3") (pintype "passive"))
      (node (ref "LS1") (pin "1") (pinfunction "A_1") (pintype "passive"))
      (node (ref "P1") (pin "10") (pinfunction "10_10") (pintype "passive"))
      (node (ref "Q12") (pin "2") (pinfunction "E_2") (pintype "passive"))
      (node (ref "Q13") (pin "2") (pinfunction "E_2") (pintype "passive"))
      (node (ref "Q14") (pin "2") (pinfunction "E_2") (pintype "passive"))
      (node (ref "Q18") (pin "2") (pinfunction "E_2") (pintype "passive"))
      (node (ref "Q19") (pin "2") (pinfunction "E_2") (pintype "passive"))
      (node (ref "Q22") (pin "2") (pinfunction "E_2") (pintype "passive"))
      (node (ref "Q4") (pin "2") (pinfunction "E_2") (pintype "passive"))
      (node (ref "Q5") (pin "2") (pinfunction "E_2") (pintype "passive"))
      (node (ref "Q6") (pin "2") (pinfunction "E_2") (pintype "passive"))
      (node (ref "Q7") (pin "2") (pinfunction "E_2") (pintype "passive"))
      (node (ref "R15") (pin "2") (pinfunction "2_2") (pintype "passive"))
      (node (ref "R16") (pin "2") (pinfunction "2_2") (pintype "passive"))
      (node (ref "R17") (pin "2") (pinfunction "2_2") (pintype "passive"))
      (node (ref "R21") (pin "2") (pinfunction "2_2") (pintype "passive"))
      (node (ref "R30") (pin "2") (pinfunction "2_2") (pintype "passive"))
      (node (ref "R31") (pin "2") (pinfunction "2_2") (pintype "passive"))
      (node (ref "R32") (pin "2") (pinfunction "2_2") (pintype "passive"))
      (node (ref "R42") (pin "2") (pinfunction "2_2") (pintype "passive"))
      (node (ref "R43") (pin "2") (pinfunction "2_2") (pintype "passive"))
      (node (ref "R46") (pin "2") (pinfunction "2_2") (pintype "passive"))
      (node (ref "R8") (pin "1") (pinfunction "1_1") (pintype "passive"))
      (node (ref "T1") (pin "1") (pinfunction "A_1") (pintype "passive"))
      (node (ref "T2") (pin "1") (pinfunction "A_1") (pintype "passive"))
      (node (ref "U1") (pin "5") (pinfunction "GND_5") (pintype "passive"))
      (node (ref "U2") (pin "2") (pinfunction "GND_2") (pintype "passive"))
      (node (ref "U2") (pin "3") (pinfunction "GND_3") (pintype "passive"))
      (node (ref "U2") (pin "6") (pinfunction "GND_6") (pintype "passive"))
      (node (ref "U3") (pin "12") (pinfunction "GND_12") (pintype "power_in"))
      (node (ref "U4") (pin "1") (pinfunction "GND_1") (pintype "passive"))
    )
    (net (code "61") (name "Net-(D1-A)") (class "Default")
      (node (ref "24V") (pin "1") (pinfunction "1_1") (pintype "passive"))
      (node (ref "D1") (pin "1") (pinfunction "A_1") (pintype "passive"))
    )
    (net (code "62") (name "Net-(D1-K)") (class "Default")
      (node (ref "D1") (pin "2") (pinfunction "K_2") (pintype "passive"))
      (node (ref "R1") (pin "1") (pinfunction "1_1") (pintype "passive"))
    )
    (net (code "63") (name "Net-(D2-B)") (class "Default")
      (node (ref "D2") (pin "4") (pinfunction "B_4") (pintype "passive"))
      (node (ref "D3") (pin "4") (pinfunction "B_4") (pintype "passive"))
      (node (ref "D4") (pin "4") (pinfunction "B_4") (pintype "passive"))
      (node (ref "D6") (pin "4") (pinfunction "B_4") (pintype "passive"))
      (node (ref "R11") (pin "1") (pinfunction "1_1") (pintype "passive"))
    )
    (net (code "64") (name "Net-(D2-G)") (class "Default")
      (node (ref "D2") (pin "5") (pinfunction "G_5") (pintype "passive"))
      (node (ref "D3") (pin "5") (pinfunction "G_5") (pintype "passive"))
      (node (ref "D4") (pin "5") (pinfunction "G_5") (pintype "passive"))
      (node (ref "D6") (pin "5") (pinfunction "G_5") (pintype "passive"))
      (node (ref "R9") (pin "1") (pinfunction "1_1") (pintype "passive"))
    )
    (net (code "65") (name "Net-(D2-R)") (class "Default")
      (node (ref "D2") (pin "6") (pinfunction "R_6") (pintype "passive"))
      (node (ref "D3") (pin "6") (pinfunction "R_6") (pintype "passive"))
      (node (ref "D4") (pin "6") (pinfunction "R_6") (pintype "passive"))
      (node (ref "D6") (pin "6") (pinfunction "R_6") (pintype "passive"))
      (node (ref "R3") (pin "1") (pinfunction "1_1") (pintype "passive"))
    )
    (net (code "66") (name "Net-(D5-K)") (class "Default")
      (node (ref "C4") (pin "2") (pinfunction "2_2") (pintype "passive"))
      (node (ref "D5") (pin "2") (pinfunction "K_2") (pintype "passive"))
      (node (ref "L1") (pin "1") (pinfunction "1_1") (pintype "passive"))
      (node (ref "U2") (pin "8") (pinfunction "VSW_8") (pintype "passive"))
    )
    (net (code "67") (name "Net-(D7-A)") (class "Default")
      (node (ref "D7") (pin "1") (pinfunction "A_1") (pintype "passive"))
      (node (ref "R12") (pin "1") (pinfunction "1_1") (pintype "passive"))
    )
    (net (code "68") (name "Net-(D8-A)") (class "Default")
      (node (ref "D8") (pin "1") (pinfunction "A_1") (pintype "passive"))
      (node (ref "R13") (pin "1") (pinfunction "1_1") (pintype "passive"))
    )
    (net (code "69") (name "Net-(D9-A)") (class "Default")
      (node (ref "D9") (pin "1") (pinfunction "A_1") (pintype "passive"))
      (node (ref "R14") (pin "1") (pinfunction "1_1") (pintype "passive"))
    )
    (net (code "70") (name "Net-(D10-A)") (class "Default")
      (node (ref "D10") (pin "1") (pinfunction "A_1") (pintype "passive"))
      (node (ref "R27") (pin "1") (pinfunction "1_1") (pintype "passive"))
    )
    (net (code "71") (name "Net-(D11-A)") (class "Default")
      (node (ref "D11") (pin "1") (pinfunction "A_1") (pintype "passive"))
      (node (ref "R28") (pin "1") (pinfunction "1_1") (pintype "passive"))
    )
    (net (code "72") (name "Net-(D12-A)") (class "Default")
      (node (ref "D12") (pin "1") (pinfunction "A_1") (pintype "passive"))
      (node (ref "R29") (pin "1") (pinfunction "1_1") (pintype "passive"))
    )
    (net (code "73") (name "Net-(D13-A)") (class "Default")
      (node (ref "D13") (pin "1") (pinfunction "A_1") (pintype "passive"))
      (node (ref "R39") (pin "1") (pinfunction "1_1") (pintype "passive"))
    )
    (net (code "74") (name "Net-(D14-A)") (class "Default")
      (node (ref "D14") (pin "1") (pinfunction "A_1") (pintype "passive"))
      (node (ref "R40") (pin "1") (pinfunction "1_1") (pintype "passive"))
    )
    (net (code "75") (name "Net-(D15-A)") (class "Default")
      (node (ref "D15") (pin "1") (pinfunction "A_1") (pintype "passive"))
      (node (ref "R41") (pin "1") (pinfunction "1_1") (pintype "passive"))
    )
    (net (code "76") (name "Net-(D16-A)") (class "Default")
      (node (ref "D16") (pin "1") (pinfunction "A_1") (pintype "passive"))
      (node (ref "R48") (pin "1") (pinfunction "1_1") (pintype "passive"))
    )
    (net (code "77") (name "Net-(D29-K)") (class "Default")
      (node (ref "D29") (pin "2") (pinfunction "K_2") (pintype "passive"))
      (node (ref "LS1") (pin "2") (pinfunction "B_2") (pintype "passive"))
      (node (ref "R56") (pin "1") (pinfunction "1_1") (pintype "passive"))
    )
    (net (code "78") (name "Net-(DO1-Pad1)") (class "Default")
      (node (ref "DO1") (pin "1") (pinfunction "1_1") (pintype "passive"))
      (node (ref "F3") (pin "2") (pinfunction "2_2") (pintype "passive"))
    )
    (net (code "79") (name "Net-(DO2-Pad1)") (class "Default")
      (node (ref "DO2") (pin "1") (pinfunction "1_1") (pintype "passive"))
      (node (ref "F4") (pin "2") (pinfunction "2_2") (pintype "passive"))
    )
    (net (code "80") (name "Net-(DO3-Pad1)") (class "Default")
      (node (ref "DO3") (pin "1") (pinfunction "1_1") (pintype "passive"))
      (node (ref "F5") (pin "2") (pinfunction "2_2") (pintype "passive"))
    )
    (net (code "81") (name "Net-(DO4-Pad1)") (class "Default")
      (node (ref "DO4") (pin "1") (pinfunction "1_1") (pintype "passive"))
      (node (ref "F6") (pin "2") (pinfunction "2_2") (pintype "passive"))
    )
    (net (code "82") (name "Net-(DO5-Pad1)") (class "Default")
      (node (ref "DO5") (pin "1") (pinfunction "1_1") (pintype "passive"))
      (node (ref "F7") (pin "2") (pinfunction "2_2") (pintype "passive"))
    )
    (net (code "83") (name "Net-(DO6-Pad1)") (class "Default")
      (node (ref "DO6") (pin "1") (pinfunction "1_1") (pintype "passive"))
      (node (ref "F8") (pin "2") (pinfunction "2_2") (pintype "passive"))
    )
    (net (code "84") (name "Net-(DO7-Pad1)") (class "Default")
      (node (ref "DO7") (pin "1") (pinfunction "1_1") (pintype "passive"))
      (node (ref "F9") (pin "2") (pinfunction "2_2") (pintype "passive"))
    )
    (net (code "85") (name "Net-(DO8-Pad1)") (class "Default")
      (node (ref "DO8") (pin "1") (pinfunction "1_1") (pintype "passive"))
      (node (ref "F10") (pin "2") (pinfunction "2_2") (pintype "passive"))
    )
    (net (code "86") (name "Net-(DO9-Pad1)") (class "Default")
      (node (ref "DO9") (pin "1") (pinfunction "1_1") (pintype "passive"))
      (node (ref "F11") (pin "2") (pinfunction "2_2") (pintype "passive"))
    )
    (net (code "87") (name "Net-(DO10-Pad1)") (class "Default")
      (node (ref "DO10") (pin "1") (pinfunction "1_1") (pintype "passive"))
      (node (ref "F12") (pin "2") (pinfunction "2_2") (pintype "passive"))
    )
    (net (code "88") (name "Net-(F1-Pad2)") (class "Default")
      (node (ref "F1") (pin "2") (pinfunction "2_2") (pintype "passive"))
      (node (ref "M485A") (pin "1") (pinfunction "1_1") (pintype "passive"))
    )
    (net (code "89") (name "Net-(F2-Pad2)") (class "Default")
      (node (ref "F2") (pin "2") (pinfunction "2_2") (pintype "passive"))
      (node (ref "M485B") (pin "1") (pinfunction "1_1") (pintype "passive"))
    )
    (net (code "90") (name "Net-(Q1-B)") (class "Default")
      (node (ref "Q1") (pin "1") (pinfunction "B_1") (pintype "passive"))
      (node (ref "R2") (pin "2") (pinfunction "2_2") (pintype "passive"))
    )
    (net (code "91") (name "Net-(Q1-C)") (class "Default")
      (node (ref "Q1") (pin "3") (pinfunction "C_3") (pintype "passive"))
      (node (ref "R3") (pin "2") (pinfunction "2_2") (pintype "passive"))
    )
    (net (code "92") (name "Net-(Q2-B)") (class "Default")
      (node (ref "Q2") (pin "1") (pinfunction "B_1") (pintype "passive"))
      (node (ref "R4") (pin "2") (pinfunction "2_2") (pintype "passive"))
    )
    (net (code "93") (name "Net-(Q2-C)") (class "Default")
      (node (ref "Q2") (pin "3") (pinfunction "C_3") (pintype "passive"))
      (node (ref "R9") (pin "2") (pinfunction "2_2") (pintype "passive"))
    )
    (net (code "94") (name "Net-(Q3-B)") (class "Default")
      (node (ref "Q3") (pin "1") (pinfunction "B_1") (pintype "passive"))
      (node (ref "R10") (pin "2") (pinfunction "2_2") (pintype "passive"))
    )
    (net (code "95") (name "Net-(Q3-C)") (class "Default")
      (node (ref "Q3") (pin "3") (pinfunction "C_3") (pintype "passive"))
      (node (ref "R11") (pin "2") (pinfunction "2_2") (pintype "passive"))
    )
    (net (code "96") (name "Net-(Q4-B)") (class "Default")
      (node (ref "Q4") (pin "1") (pinfunction "B_1") (pintype "passive"))
      (node (ref "R18") (pin "1") (pinfunction "1_1") (pintype "passive"))
    )
    (net (code "97") (name "Net-(Q5-B)") (class "Default")
      (node (ref "Q5") (pin "1") (pinfunction "B_1") (pintype "passive"))
      (node (ref "R20") (pin "2") (pinfunction "2_2") (pintype "passive"))
    )
    (net (code "98") (name "Net-(Q6-B)") (class "Default")
      (node (ref "Q6") (pin "1") (pinfunction "B_1") (pintype "passive"))
      (node (ref "R19") (pin "1") (pinfunction "1_1") (pintype "passive"))
    )
    (net (code "99") (name "Net-(Q7-B)") (class "Default")
      (node (ref "Q7") (pin "1") (pinfunction "B_1") (pintype "passive"))
      (node (ref "R22") (pin "1") (pinfunction "1_1") (pintype "passive"))
    )
    (net (code "100") (name "Net-(Q12-B)") (class "Default")
      (node (ref "Q12") (pin "1") (pinfunction "B_1") (pintype "passive"))
      (node (ref "R33") (pin "1") (pinfunction "1_1") (pintype "passive"))
    )
    (net (code "101") (name "Net-(Q13-B)") (class "Default")
      (node (ref "Q13") (pin "1") (pinfunction "B_1") (pintype "passive"))
      (node (ref "R34") (pin "1") (pinfunction "1_1") (pintype "passive"))
    )
    (net (code "102") (name "Net-(Q14-B)") (class "Default")
      (node (ref "Q14") (pin "1") (pinfunction "B_1") (pintype "passive"))
      (node (ref "R35") (pin "1") (pinfunction "1_1") (pintype "passive"))
    )
    (net (code "103") (name "Net-(Q18-B)") (class "Default")
      (node (ref "Q18") (pin "1") (pinfunction "B_1") (pintype "passive"))
      (node (ref "R44") (pin "1") (pinfunction "1_1") (pintype "passive"))
    )
    (net (code "104") (name "Net-(Q19-B)") (class "Default")
      (node (ref "Q19") (pin "1") (pinfunction "B_1") (pintype "passive"))
      (node (ref "R45") (pin "1") (pinfunction "1_1") (pintype "passive"))
    )
    (net (code "105") (name "Net-(Q22-B)") (class "Default")
      (node (ref "Q22") (pin "1") (pinfunction "B_1") (pintype "passive"))
      (node (ref "R47") (pin "1") (pinfunction "1_1") (pintype "passive"))
    )
    (net (code "106") (name "Net-(Q24-B)") (class "Default")
      (node (ref "Q24") (pin "1") (pinfunction "B_1") (pintype "passive"))
      (node (ref "R54") (pin "2") (pinfunction "2_2") (pintype "passive"))
    )
    (net (code "107") (name "Net-(Q24-C)") (class "Default")
      (node (ref "Q24") (pin "3") (pinfunction "C_3") (pintype "passive"))
      (node (ref "R56") (pin "2") (pinfunction "2_2") (pintype "passive"))
    )
    (net (code "108") (name "Net-(T1-K)") (class "Default")
      (node (ref "F2") (pin "1") (pinfunction "1_1") (pintype "passive"))
      (node (ref "R5") (pin "1") (pinfunction "1_1") (pintype "passive"))
      (node (ref "T1") (pin "2") (pinfunction "K_2") (pintype "passive"))
    )
    (net (code "109") (name "Net-(T2-K)") (class "Default")
      (node (ref "F1") (pin "1") (pinfunction "1_1") (pintype "passive"))
      (node (ref "R6") (pin "1") (pinfunction "1_1") (pintype "passive"))
      (node (ref "T2") (pin "2") (pinfunction "K_2") (pintype "passive"))
    )
    (net (code "110") (name "Net-(U1-A)") (class "Default")
      (node (ref "R6") (pin "2") (pinfunction "2_2") (pintype "passive"))
      (node (ref "U1") (pin "6") (pinfunction "A_6") (pintype "passive"))
    )
    (net (code "111") (name "Net-(U1-B)") (class "Default")
      (node (ref "R5") (pin "2") (pinfunction "2_2") (pintype "passive"))
      (node (ref "U1") (pin "7") (pinfunction "B_7") (pintype "passive"))
    )
    (net (code "112") (name "Net-(U2-CB)") (class "Default")
      (node (ref "C4") (pin "1") (pinfunction "1_1") (pintype "passive"))
      (node (ref "U2") (pin "1") (pinfunction "CB_1") (pintype "passive"))
    )
    (net (code "113") (name "Net-(U2-FB)") (class "Default")
      (node (ref "R7") (pin "1") (pinfunction "1_1") (pintype "passive"))
      (node (ref "R8") (pin "2") (pinfunction "2_2") (pintype "passive"))
      (node (ref "U2") (pin "4") (pinfunction "FB_4") (pintype "passive"))
    )
    (net (code "114") (name "VDD_+5V") (class "Default")
      (node (ref "C1") (pin "2") (pinfunction "2_2") (pintype "passive"))
      (node (ref "C2") (pin "1") (pinfunction "1_1") (pintype "passive"))
      (node (ref "C3") (pin "2") (pinfunction "2_2") (pintype "passive"))
      (node (ref "C5") (pin "1") (pinfunction "1_1") (pintype "passive"))
      (node (ref "C6") (pin "1") (pinfunction "1_1") (pintype "passive"))
      (node (ref "C7") (pin "1") (pinfunction "1_1") (pintype "passive"))
      (node (ref "J1") (pin "4") (pinfunction "4_4") (pintype "passive"))
      (node (ref "L1") (pin "2") (pinfunction "2_2") (pintype "passive"))
      (node (ref "Q1") (pin "2") (pinfunction "E_2") (pintype "passive"))
      (node (ref "Q2") (pin "2") (pinfunction "E_2") (pintype "passive"))
      (node (ref "Q24") (pin "2") (pinfunction "E_2") (pintype "passive"))
      (node (ref "Q3") (pin "2") (pinfunction "E_2") (pintype "passive"))
      (node (ref "R7") (pin "2") (pinfunction "2_2") (pintype "passive"))
      (node (ref "U1") (pin "8") (pinfunction "VCC_8") (pintype "passive"))
      (node (ref "U3") (pin "10") (pinfunction "VCC_10") (pintype "power_in"))
      (node (ref "U4") (pin "3") (pinfunction "IN_3") (pintype "passive"))
    )
    (net (code "115") (name "unconnected-(U2-ON{slash}OFF-Pad5)") (class "Default")
      (node (ref "U2") (pin "5") (pinfunction "ON/OFF_5") (pintype "passive"))
    )
    (net (code "116") (name "unconnected-(U3-INT0{slash}P3.2-Pad15)") (class "Default")
      (node (ref "U3") (pin "15") (pinfunction "INT0/P3.2_15") (pintype "passive"))
    )
    (net (code "117") (name "unconnected-(U3-MISO_2{slash}P2.2-Pad23)") (class "Default")
      (node (ref "U3") (pin "23") (pinfunction "MISO_2/P2.2_23") (pintype "passive"))
    )
    (net (code "118") (name "unconnected-(U3-MOSI_2{slash}P2.3-Pad24)") (class "Default")
      (node (ref "U3") (pin "24") (pinfunction "MOSI_2/P2.3_24") (pintype "passive"))
    )
    (net (code "119") (name "unconnected-(U3-SCLK_2{slash}P2.1-Pad22)") (class "Default")
      (node (ref "U3") (pin "22") (pinfunction "SCLK_2/P2.1_22") (pintype "passive"))
    )
  )
)
